# H-bridge.net
KiCad netlist of a schematic drawn in EAGLE
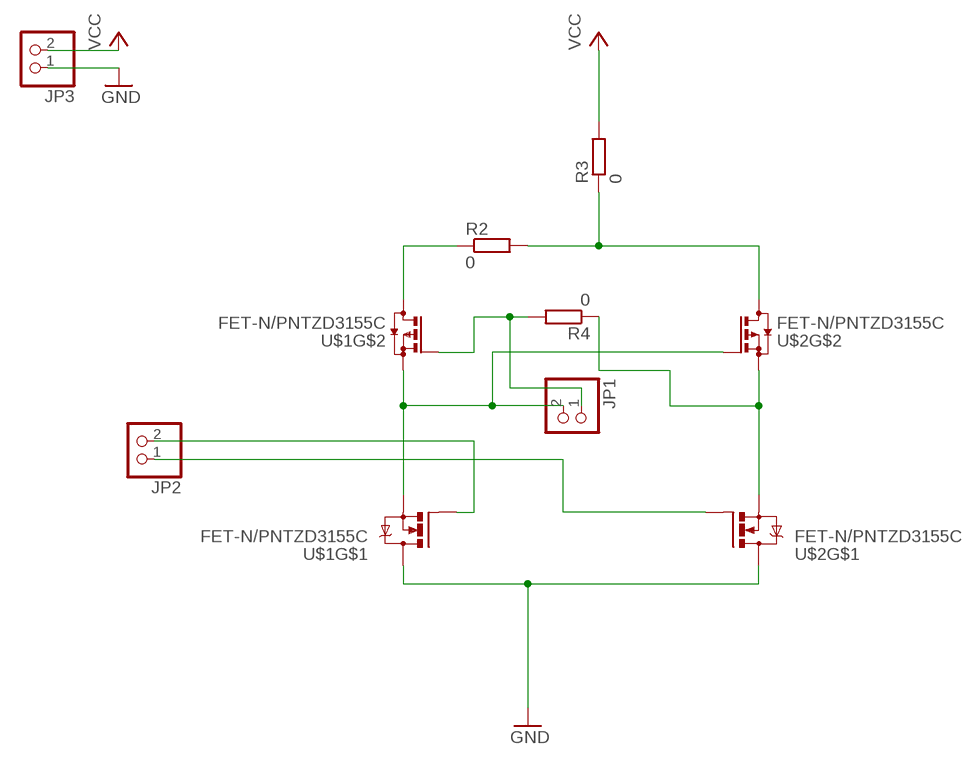
[diagram p0: schematic, sheet 1]

(export (version "E")
  (design (tool "Eeschema 10.0.6"))
  (components
    (comp (ref "JP1")
      (value "PINHD-1X2")
      (footprint "eagle-import:1X02")
      (libsource (lib "eagle-import") (part "PINHD-1X2"))
    )
    (comp (ref "JP2")
      (value "PINHD-1X2")
      (footprint "eagle-import:1X02")
      (libsource (lib "eagle-import") (part "PINHD-1X2"))
    )
    (comp (ref "JP3")
      (value "PINHD-1X2")
      (footprint "eagle-import:1X02")
      (libsource (lib "eagle-import") (part "PINHD-1X2"))
    )
    (comp (ref "R2")
      (value "0")
      (footprint "eagle-import:R0805")
      (libsource (lib "eagle-import") (part "R_0805"))
    )
    (comp (ref "R3")
      (value "0")
      (footprint "eagle-import:R0805")
      (libsource (lib "eagle-import") (part "R_0805"))
    )
    (comp (ref "R4")
      (value "0")
      (footprint "eagle-import:R0805")
      (libsource (lib "eagle-import") (part "R_0805"))
    )
    (comp (ref "U$1")
      (value "FET-N/PNTZD3155C")
      (footprint "eagle-import:SOT-563")
      (libsource (lib "eagle-import") (part "FET-N/PNTZD3155C"))
    )
    (comp (ref "U$2")
      (value "FET-N/PNTZD3155C")
      (footprint "eagle-import:SOT-563")
      (libsource (lib "eagle-import") (part "FET-N/PNTZD3155C"))
    )
  )
  (nets
    (net (code "1") (name "GND") (class "Default")
      (node (ref "JP3") (pin "1") (pinfunction "1_1") (pintype "passive"))
      (node (ref "U$1") (pin "6") (pinfunction "D_6") (pintype "passive"))
      (node (ref "U$2") (pin "6") (pinfunction "D_6") (pintype "passive"))
    )
    (net (code "2") (name "Net-(U$1A-G)") (class "Default")
      (node (ref "JP2") (pin "2") (pinfunction "2_2") (pintype "passive"))
      (node (ref "U$1") (pin "2") (pinfunction "G_2") (pintype "passive"))
    )
    (net (code "3") (name "Net-(U$1A-S)") (class "Default")
      (node (ref "JP1") (pin "2") (pinfunction "2_2") (pintype "passive"))
      (node (ref "U$1") (pin "1") (pinfunction "S_1") (pintype "passive"))
      (node (ref "U$1") (pin "4") (pinfunction "S_4") (pintype "passive"))
      (node (ref "U$2") (pin "5") (pinfunction "G_5") (pintype "passive"))
    )
    (net (code "4") (name "Net-(U$1B-D)") (class "Default")
      (node (ref "R2") (pin "1") (pinfunction "1_1") (pintype "passive"))
      (node (ref "U$1") (pin "3") (pinfunction "D_3") (pintype "passive"))
    )
    (net (code "5") (name "Net-(U$1B-G)") (class "Default")
      (node (ref "JP1") (pin "1") (pinfunction "1_1") (pintype "passive"))
      (node (ref "R4") (pin "2") (pinfunction "2_2") (pintype "passive"))
      (node (ref "U$1") (pin "5") (pinfunction "G_5") (pintype "passive"))
    )
    (net (code "6") (name "Net-(U$2A-G)") (class "Default")
      (node (ref "JP2") (pin "1") (pinfunction "1_1") (pintype "passive"))
      (node (ref "U$2") (pin "2") (pinfunction "G_2") (pintype "passive"))
    )
    (net (code "7") (name "Net-(U$2A-S)") (class "Default")
      (node (ref "R4") (pin "1") (pinfunction "1_1") (pintype "passive"))
      (node (ref "U$2") (pin "1") (pinfunction "S_1") (pintype "passive"))
      (node (ref "U$2") (pin "4") (pinfunction "S_4") (pintype "passive"))
    )
    (net (code "8") (name "Net-(U$2B-D)") (class "Default")
      (node (ref "R2") (pin "2") (pinfunction "2_2") (pintype "passive"))
      (node (ref "R3") (pin "1") (pinfunction "1_1") (pintype "passive"))
      (node (ref "U$2") (pin "3") (pinfunction "D_3") (pintype "passive"))
    )
    (net (code "9") (name "VCC") (class "Default")
      (node (ref "JP3") (pin "2") (pinfunction "2_2") (pintype "passive"))
      (node (ref "R3") (pin "2") (pinfunction "2_2") (pintype "passive"))
    )
  )
)
